# DOG_DisplayBreakout_pth_smd.net
KiCad netlist of a schematic drawn in EAGLE
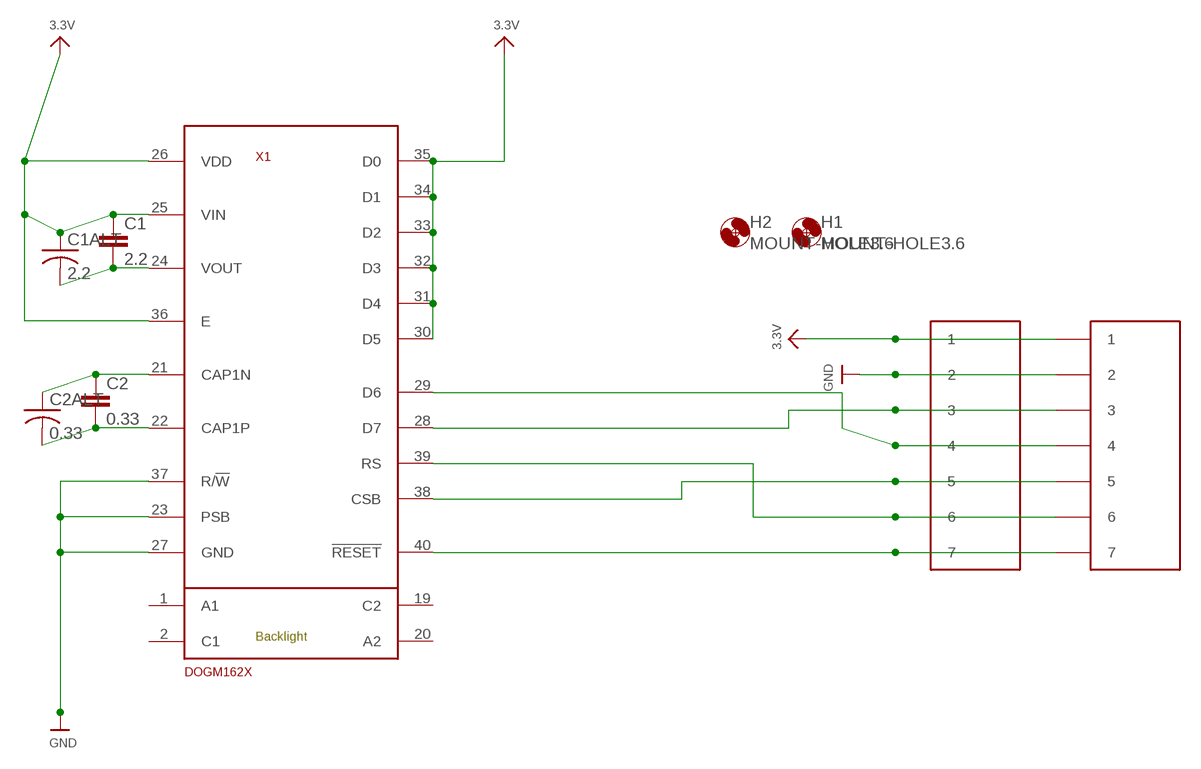
[diagram p0: schematic, sheet 1]

(export (version "E")
  (design (tool "Eeschema 10.0.6"))
  (components
    (comp (ref "C1")
      (value "2.2")
      (footprint "eagle-import:0805_BIGGERPAD-OK")
      (libsource (lib "eagle-import") (part "CAPACITOR0805"))
    )
    (comp (ref "C1ALT")
      (value "2.2")
      (footprint "eagle-import:C050-035X075")
      (libsource (lib "eagle-import") (part "rcl_C-US050-035X075"))
    )
    (comp (ref "C2")
      (value "0.33")
      (footprint "eagle-import:0805_BIGGERPAD-OK")
      (libsource (lib "eagle-import") (part "CAPACITOR0805"))
    )
    (comp (ref "C2ALT")
      (value "0.33")
      (footprint "eagle-import:C050-024X044")
      (libsource (lib "eagle-import") (part "C-US050-024X044"))
    )
    (comp (ref "CN1")
      (value "JST_S7B-PH-SM4-TB")
      (footprint "eagle-import:JST_S7B-PH-SM4-TB")
      (libsource (lib "eagle-import") (part "JST_S7B-PH-SM4-TB"))
    )
    (comp (ref "CN1ALT")
      (value "JST_S7B-PH-K-S")
      (footprint "eagle-import:JST_S7B-PH-K-S")
      (libsource (lib "eagle-import") (part "JST_S7B-PH-K-S"))
    )
    (comp (ref "H1")
      (value "MOUNT-HOLE3.6")
      (footprint "eagle-import:HOLE3,6")
      (libsource (lib "eagle-import") (part "MOUNT-HOLE3.6"))
    )
    (comp (ref "H2")
      (value "MOUNT-HOLE3.6")
      (footprint "eagle-import:HOLE3,6")
      (libsource (lib "eagle-import") (part "MOUNT-HOLE3.6"))
    )
    (comp (ref "X1")
      (value "DOGM162X")
      (footprint "eagle-import:DOGM162X")
      (libsource (lib "eagle-import") (part "DOGM162X"))
    )
  )
  (nets
    (net (code "1") (name "3.3V") (class "Default")
      (node (ref "C1") (pin "1") (pinfunction "1_1") (pintype "passive"))
      (node (ref "C1ALT") (pin "1") (pinfunction "1_1") (pintype "passive"))
      (node (ref "CN1") (pin "P$1") (pinfunction "1_P$1") (pintype "bidirectional"))
      (node (ref "CN1ALT") (pin "P1") (pinfunction "1_P1") (pintype "bidirectional"))
      (node (ref "X1") (pin "25") (pinfunction "VIN_25") (pintype "bidirectional"))
      (node (ref "X1") (pin "26") (pinfunction "VDD_26") (pintype "bidirectional"))
      (node (ref "X1") (pin "30") (pinfunction "D5_30") (pintype "bidirectional"))
      (node (ref "X1") (pin "31") (pinfunction "D4_31") (pintype "bidirectional"))
      (node (ref "X1") (pin "32") (pinfunction "D3_32") (pintype "bidirectional"))
      (node (ref "X1") (pin "33") (pinfunction "D2_33") (pintype "bidirectional"))
      (node (ref "X1") (pin "34") (pinfunction "D1_34") (pintype "bidirectional"))
      (node (ref "X1") (pin "35") (pinfunction "D0_35") (pintype "bidirectional"))
      (node (ref "X1") (pin "36") (pinfunction "E_36") (pintype "bidirectional"))
    )
    (net (code "2") (name "GND") (class "Default")
      (node (ref "CN1") (pin "P$2") (pinfunction "2_P$2") (pintype "bidirectional"))
      (node (ref "CN1ALT") (pin "P2") (pinfunction "2_P2") (pintype "bidirectional"))
      (node (ref "X1") (pin "23") (pinfunction "PSB_23") (pintype "bidirectional"))
      (node (ref "X1") (pin "27") (pinfunction "GND_27") (pintype "bidirectional"))
      (node (ref "X1") (pin "37") (pinfunction "R/~{W}_37") (pintype "bidirectional"))
    )
    (net (code "3") (name "Net-(CN1-3)") (class "Default")
      (node (ref "CN1") (pin "P$3") (pinfunction "3_P$3") (pintype "bidirectional"))
      (node (ref "CN1ALT") (pin "P3") (pinfunction "3_P3") (pintype "bidirectional"))
      (node (ref "X1") (pin "28") (pinfunction "D7_28") (pintype "bidirectional"))
    )
    (net (code "4") (name "Net-(CN1-4)") (class "Default")
      (node (ref "CN1") (pin "P$4") (pinfunction "4_P$4") (pintype "bidirectional"))
      (node (ref "CN1ALT") (pin "P4") (pinfunction "4_P4") (pintype "bidirectional"))
      (node (ref "X1") (pin "29") (pinfunction "D6_29") (pintype "bidirectional"))
    )
    (net (code "5") (name "Net-(CN1-5)") (class "Default")
      (node (ref "CN1") (pin "P$5") (pinfunction "5_P$5") (pintype "bidirectional"))
      (node (ref "CN1ALT") (pin "P5") (pinfunction "5_P5") (pintype "bidirectional"))
      (node (ref "X1") (pin "38") (pinfunction "CSB_38") (pintype "bidirectional"))
    )
    (net (code "6") (name "Net-(CN1-6)") (class "Default")
      (node (ref "CN1") (pin "P$6") (pinfunction "6_P$6") (pintype "bidirectional"))
      (node (ref "CN1ALT") (pin "P6") (pinfunction "6_P6") (pintype "bidirectional"))
      (node (ref "X1") (pin "39") (pinfunction "RS_39") (pintype "bidirectional"))
    )
    (net (code "7") (name "Net-(CN1-7)") (class "Default")
      (node (ref "CN1") (pin "P$7") (pinfunction "7_P$7") (pintype "bidirectional"))
      (node (ref "CN1ALT") (pin "P7") (pinfunction "7_P7") (pintype "bidirectional"))
      (node (ref "X1") (pin "40") (pinfunction "~{RESET}_40") (pintype "bidirectional"))
    )
    (net (code "8") (name "Net-(X1-CAP1N)") (class "Default")
      (node (ref "C2") (pin "1") (pinfunction "1_1") (pintype "passive"))
      (node (ref "C2ALT") (pin "1") (pinfunction "1_1") (pintype "passive"))
      (node (ref "X1") (pin "21") (pinfunction "CAP1N_21") (pintype "bidirectional"))
    )
    (net (code "9") (name "Net-(X1-CAP1P)") (class "Default")
      (node (ref "C2") (pin "2") (pinfunction "2_2") (pintype "passive"))
      (node (ref "C2ALT") (pin "2") (pinfunction "2_2") (pintype "passive"))
      (node (ref "X1") (pin "22") (pinfunction "CAP1P_22") (pintype "bidirectional"))
    )
    (net (code "10") (name "Net-(X1-VOUT)") (class "Default")
      (node (ref "C1") (pin "2") (pinfunction "2_2") (pintype "passive"))
      (node (ref "C1ALT") (pin "2") (pinfunction "2_2") (pintype "passive"))
      (node (ref "X1") (pin "24") (pinfunction "VOUT_24") (pintype "bidirectional"))
    )
    (net (code "11") (name "unconnected-(X1-A1-Pad1)") (class "Default")
      (node (ref "X1") (pin "1") (pinfunction "A1_1") (pintype "bidirectional"))
    )
    (net (code "12") (name "unconnected-(X1-A2-Pad20)") (class "Default")
      (node (ref "X1") (pin "20") (pinfunction "A2_20") (pintype "bidirectional"))
    )
    (net (code "13") (name "unconnected-(X1-C1-Pad2)") (class "Default")
      (node (ref "X1") (pin "2") (pinfunction "C1_2") (pintype "bidirectional"))
    )
    (net (code "14") (name "unconnected-(X1-C2-Pad19)") (class "Default")
      (node (ref "X1") (pin "19") (pinfunction "C2_19") (pintype "bidirectional"))
    )
  )
)
